# SparkFun_XBee-Breakout.net
KiCad netlist of a schematic drawn in EAGLE
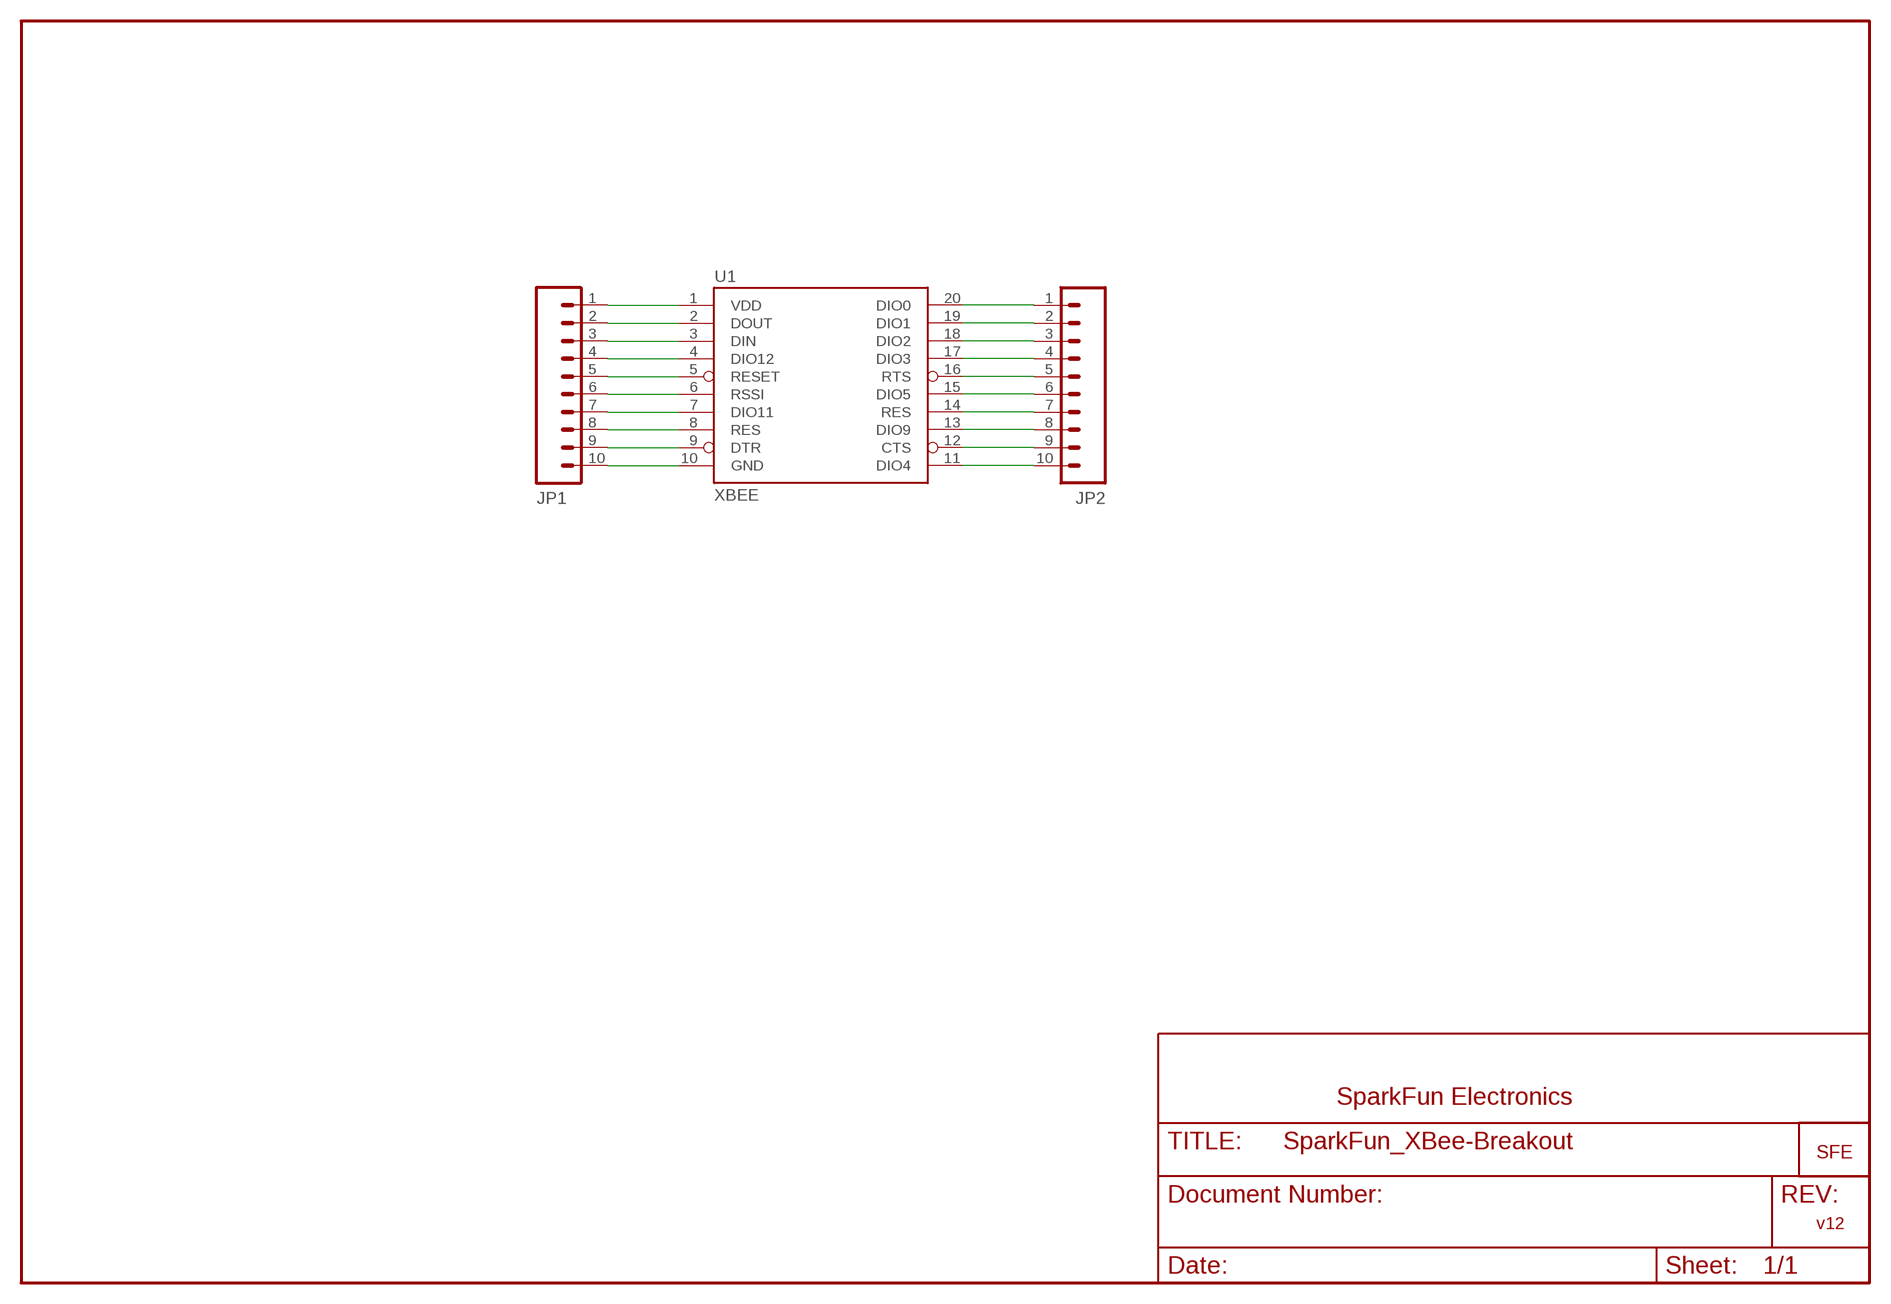
[diagram p0: schematic, sheet 1]

(export (version "E")
  (design (tool "Eeschema 10.0.6"))
  (components
    (comp (ref "JP1")
      (value "M100.1")
      (footprint "eagle-import:1X10")
      (libsource (lib "eagle-import") (part "M100.1"))
    )
    (comp (ref "JP2")
      (value "M100.1")
      (footprint "eagle-import:1X10")
      (libsource (lib "eagle-import") (part "M100.1"))
    )
    (comp (ref "U$2")
      (value "LOGO-SFENEW")
      (footprint "eagle-import:SFE-NEW-WEBLOGO")
      (libsource (lib "eagle-import") (part "LOGO-SFENEW"))
    )
    (comp (ref "U1")
      (value "XBEE")
      (footprint "eagle-import:XBEE-1")
      (libsource (lib "eagle-import") (part "XBEE-1B1"))
    )
  )
  (nets
    (net (code "1") (name "Net-(JP1-Pad8)") (class "Default")
      (node (ref "JP1") (pin "8") (pinfunction "8_8") (pintype "passive"))
      (node (ref "U1") (pin "8") (pinfunction "RES_8") (pintype "bidirectional"))
    )
    (net (code "2") (name "Net-(JP2-Pad7)") (class "Default")
      (node (ref "JP2") (pin "7") (pinfunction "7_7") (pintype "passive"))
      (node (ref "U1") (pin "14") (pinfunction "RES_14") (pintype "bidirectional"))
    )
    (net (code "3") (name "Net-(U1-CTS)") (class "Default")
      (node (ref "JP2") (pin "9") (pinfunction "9_9") (pintype "passive"))
      (node (ref "U1") (pin "12") (pinfunction "CTS_12") (pintype "output"))
    )
    (net (code "4") (name "Net-(U1-DIN)") (class "Default")
      (node (ref "JP1") (pin "3") (pinfunction "3_3") (pintype "passive"))
      (node (ref "U1") (pin "3") (pinfunction "DIN_3") (pintype "input"))
    )
    (net (code "5") (name "Net-(U1-DIO0)") (class "Default")
      (node (ref "JP2") (pin "1") (pinfunction "1_1") (pintype "passive"))
      (node (ref "U1") (pin "20") (pinfunction "DIO0_20") (pintype "bidirectional"))
    )
    (net (code "6") (name "Net-(U1-DIO1)") (class "Default")
      (node (ref "JP2") (pin "2") (pinfunction "2_2") (pintype "passive"))
      (node (ref "U1") (pin "19") (pinfunction "DIO1_19") (pintype "bidirectional"))
    )
    (net (code "7") (name "Net-(U1-DIO2)") (class "Default")
      (node (ref "JP2") (pin "3") (pinfunction "3_3") (pintype "passive"))
      (node (ref "U1") (pin "18") (pinfunction "DIO2_18") (pintype "bidirectional"))
    )
    (net (code "8") (name "Net-(U1-DIO3)") (class "Default")
      (node (ref "JP2") (pin "4") (pinfunction "4_4") (pintype "passive"))
      (node (ref "U1") (pin "17") (pinfunction "DIO3_17") (pintype "bidirectional"))
    )
    (net (code "9") (name "Net-(U1-DIO4)") (class "Default")
      (node (ref "JP2") (pin "10") (pinfunction "10_10") (pintype "passive"))
      (node (ref "U1") (pin "11") (pinfunction "DIO4_11") (pintype "bidirectional"))
    )
    (net (code "10") (name "Net-(U1-DIO5)") (class "Default")
      (node (ref "JP2") (pin "6") (pinfunction "6_6") (pintype "passive"))
      (node (ref "U1") (pin "15") (pinfunction "DIO5_15") (pintype "bidirectional"))
    )
    (net (code "11") (name "Net-(U1-DIO9)") (class "Default")
      (node (ref "JP2") (pin "8") (pinfunction "8_8") (pintype "passive"))
      (node (ref "U1") (pin "13") (pinfunction "DIO9_13") (pintype "bidirectional"))
    )
    (net (code "12") (name "Net-(U1-DIO11)") (class "Default")
      (node (ref "JP1") (pin "7") (pinfunction "7_7") (pintype "passive"))
      (node (ref "U1") (pin "7") (pinfunction "DIO11_7") (pintype "bidirectional"))
    )
    (net (code "13") (name "Net-(U1-DIO12)") (class "Default")
      (node (ref "JP1") (pin "4") (pinfunction "4_4") (pintype "passive"))
      (node (ref "U1") (pin "4") (pinfunction "DIO12_4") (pintype "bidirectional"))
    )
    (net (code "14") (name "Net-(U1-DOUT)") (class "Default")
      (node (ref "JP1") (pin "2") (pinfunction "2_2") (pintype "passive"))
      (node (ref "U1") (pin "2") (pinfunction "DOUT_2") (pintype "output"))
    )
    (net (code "15") (name "Net-(U1-DTR)") (class "Default")
      (node (ref "JP1") (pin "9") (pinfunction "9_9") (pintype "passive"))
      (node (ref "U1") (pin "9") (pinfunction "DTR_9") (pintype "bidirectional"))
    )
    (net (code "16") (name "Net-(U1-GND)") (class "Default")
      (node (ref "JP1") (pin "10") (pinfunction "10_10") (pintype "passive"))
      (node (ref "U1") (pin "10") (pinfunction "GND_10") (pintype "power_in"))
    )
    (net (code "17") (name "Net-(U1-RESET)") (class "Default")
      (node (ref "JP1") (pin "5") (pinfunction "5_5") (pintype "passive"))
      (node (ref "U1") (pin "5") (pinfunction "RESET_5") (pintype "input"))
    )
    (net (code "18") (name "Net-(U1-RSSI)") (class "Default")
      (node (ref "JP1") (pin "6") (pinfunction "6_6") (pintype "passive"))
      (node (ref "U1") (pin "6") (pinfunction "RSSI_6") (pintype "bidirectional"))
    )
    (net (code "19") (name "Net-(U1-RTS)") (class "Default")
      (node (ref "JP2") (pin "5") (pinfunction "5_5") (pintype "passive"))
      (node (ref "U1") (pin "16") (pinfunction "RTS_16") (pintype "input"))
    )
    (net (code "20") (name "Net-(U1-VDD)") (class "Default")
      (node (ref "JP1") (pin "1") (pinfunction "1_1") (pintype "passive"))
      (node (ref "U1") (pin "1") (pinfunction "VDD_1") (pintype "power_in"))
    )
  )
)
